# differentiator.net
KiCad netlist of a schematic drawn in Altium Designer
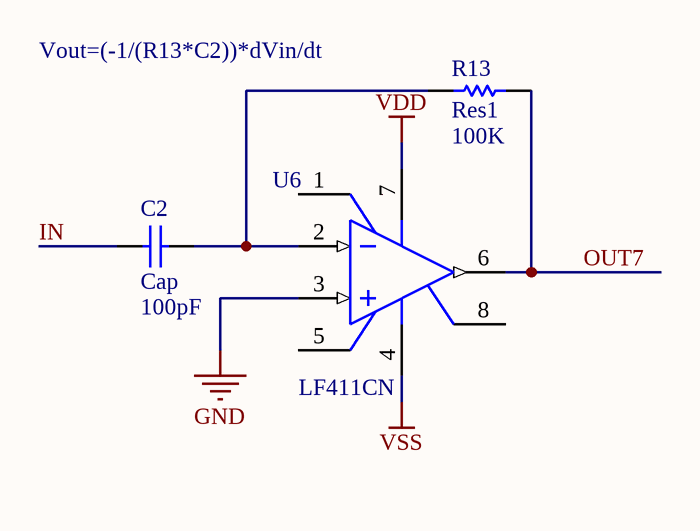
[diagram p0: differentiator.SchDoc]

(export (version "E")
  (design (tool "Eeschema 10.0.6"))
  (components
    (comp (ref "C2")
      (value "Cap")
      (footprint "RAD-0.3")
      (description "Capacitor")
      (fields (field (name "ALTIUM_VALUE") "100pF") (field (name "PUBLISHER") "Altium Limited"))
      (libsource (lib "Miscellaneous Devices") (part "Cap"))
    )
    (comp (ref "R13")
      (value "Res1")
      (footprint "AXIAL-0.3")
      (description "Resistor")
      (fields (field (name "ALTIUM_VALUE") "100K") (field (name "PUBLISHER") "Altium Limited"))
      (libsource (lib "Miscellaneous Devices") (part "Res1"))
    )
    (comp (ref "U6")
      (value "LF411CN")
      (footprint "N08E")
      (description "Low Offset, Low Drift JFET Input Operational Amplifier, 8-pin MDIP")
      (fields
        (field (name "MANUFACTURER") "National Semiconductor")
        (field (name "PUBLISHER") "Altium Limited")
      )
      (libsource (lib "NSC Amplifier") (part "LF411CN"))
    )
  )
  (nets
    (net (code "1") (name "/IN") (class "Default")
      (node (ref "C2") (pin "1") (pinfunction "1_1") (pintype "passive"))
    )
    (net (code "2") (name "/OUT7") (class "Default")
      (node (ref "R13") (pin "1") (pinfunction "1_1") (pintype "passive"))
      (node (ref "U6") (pin "6") (pinfunction "OUT_6") (pintype "output"))
    )
    (net (code "3") (name "GND") (class "Default")
      (node (ref "U6") (pin "3") (pinfunction "IN+_3") (pintype "input"))
    )
    (net (code "4") (name "Net-(U6-IN-)") (class "Default")
      (node (ref "C2") (pin "2") (pinfunction "2_2") (pintype "passive"))
      (node (ref "R13") (pin "2") (pinfunction "2_2") (pintype "passive"))
      (node (ref "U6") (pin "2") (pinfunction "IN-_2") (pintype "input"))
    )
    (net (code "5") (name "VDD") (class "Default")
      (node (ref "U6") (pin "7") (pinfunction "V+_7") (pintype "power_in"))
    )
    (net (code "6") (name "VSS") (class "Default")
      (node (ref "U6") (pin "4") (pinfunction "V-_4") (pintype "power_in"))
    )
    (net (code "7") (name "unconnected-(U6-BAL-Pad1)") (class "Default")
      (node (ref "U6") (pin "1") (pinfunction "BAL_1") (pintype "passive"))
    )
    (net (code "8") (name "unconnected-(U6-BAL-Pad5)") (class "Default")
      (node (ref "U6") (pin "5") (pinfunction "BAL_5") (pintype "passive"))
    )
    (net (code "9") (name "unconnected-(U6-NC-Pad8)") (class "Default")
      (node (ref "U6") (pin "8") (pinfunction "NC_8") (pintype "passive"))
    )
  )
)
